# esp-boardlet.net
KiCad netlist of a schematic drawn in EAGLE
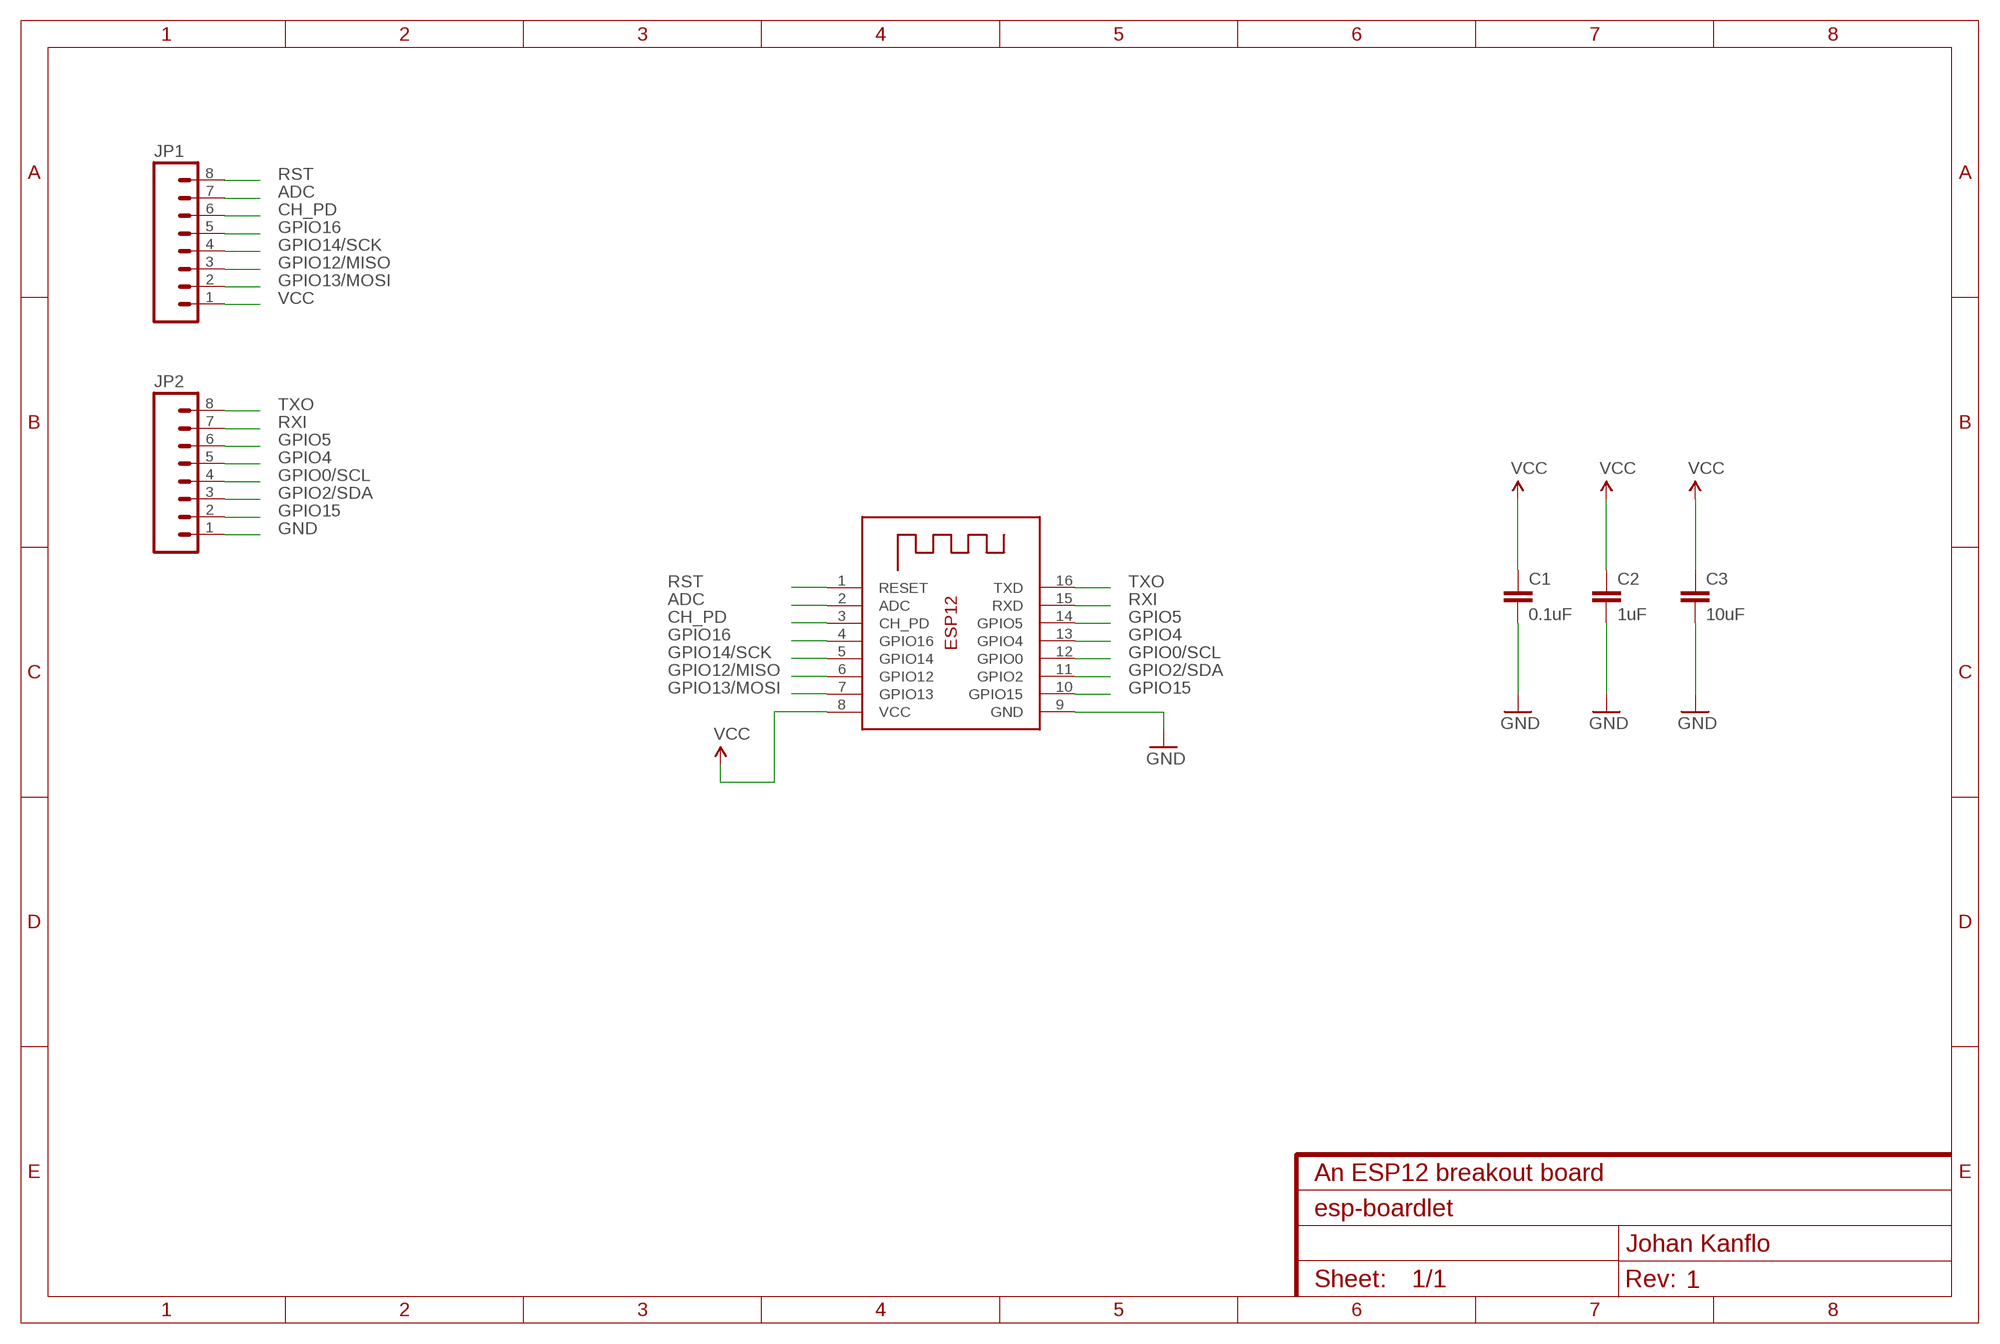
[diagram p0: schematic, sheet 1]

(export (version "E")
  (design (tool "Eeschema 10.0.6"))
  (components
    (comp (ref "C1")
      (value "0.1uF")
      (footprint "eagle-import:0603-CAP")
      (libsource (lib "eagle-import") (part "CAP0603-CAP"))
    )
    (comp (ref "C2")
      (value "1uF")
      (footprint "eagle-import:0603-CAP")
      (libsource (lib "eagle-import") (part "CAP0603-CAP"))
    )
    (comp (ref "C3")
      (value "10uF")
      (footprint "eagle-import:0603-CAP")
      (libsource (lib "eagle-import") (part "CAP0603-CAP"))
    )
    (comp (ref "JP1")
      (value "M08")
      (footprint "eagle-import:1X08_ROUND")
      (libsource (lib "eagle-import") (part "M08"))
    )
    (comp (ref "JP2")
      (value "M08")
      (footprint "eagle-import:1X08_ROUND")
      (libsource (lib "eagle-import") (part "M08"))
    )
    (comp (ref "X1")
      (value "ESP-12")
      (footprint "eagle-import:ESP-12")
      (libsource (lib "eagle-import") (part "ESP-12"))
    )
  )
  (nets
    (net (code "1") (name "/ADC") (class "Default")
      (node (ref "JP1") (pin "7") (pinfunction "7_7") (pintype "passive"))
      (node (ref "X1") (pin "2") (pinfunction "ADC_2") (pintype "passive"))
    )
    (net (code "2") (name "/CH_PD") (class "Default")
      (node (ref "JP1") (pin "6") (pinfunction "6_6") (pintype "passive"))
      (node (ref "X1") (pin "3") (pinfunction "CH_PD_3") (pintype "input"))
    )
    (net (code "3") (name "/GPIO0{slash}SCL") (class "Default")
      (node (ref "JP2") (pin "4") (pinfunction "4_4") (pintype "passive"))
      (node (ref "X1") (pin "12") (pinfunction "GPIO0_12") (pintype "bidirectional"))
    )
    (net (code "4") (name "/GPIO2{slash}SDA") (class "Default")
      (node (ref "JP2") (pin "3") (pinfunction "3_3") (pintype "passive"))
      (node (ref "X1") (pin "11") (pinfunction "GPIO2_11") (pintype "bidirectional"))
    )
    (net (code "5") (name "/GPIO4") (class "Default")
      (node (ref "JP2") (pin "5") (pinfunction "5_5") (pintype "passive"))
      (node (ref "X1") (pin "13") (pinfunction "GPIO4_13") (pintype "bidirectional"))
    )
    (net (code "6") (name "/GPIO5") (class "Default")
      (node (ref "JP2") (pin "6") (pinfunction "6_6") (pintype "passive"))
      (node (ref "X1") (pin "14") (pinfunction "GPIO5_14") (pintype "bidirectional"))
    )
    (net (code "7") (name "/GPIO12{slash}MISO") (class "Default")
      (node (ref "JP1") (pin "3") (pinfunction "3_3") (pintype "passive"))
      (node (ref "X1") (pin "6") (pinfunction "GPIO12_6") (pintype "bidirectional"))
    )
    (net (code "8") (name "/GPIO13{slash}MOSI") (class "Default")
      (node (ref "JP1") (pin "2") (pinfunction "2_2") (pintype "passive"))
      (node (ref "X1") (pin "7") (pinfunction "GPIO13_7") (pintype "bidirectional"))
    )
    (net (code "9") (name "/GPIO14{slash}SCK") (class "Default")
      (node (ref "JP1") (pin "4") (pinfunction "4_4") (pintype "passive"))
      (node (ref "X1") (pin "5") (pinfunction "GPIO14_5") (pintype "bidirectional"))
    )
    (net (code "10") (name "/GPIO15") (class "Default")
      (node (ref "JP2") (pin "2") (pinfunction "2_2") (pintype "passive"))
      (node (ref "X1") (pin "10") (pinfunction "GPIO15_10") (pintype "bidirectional"))
    )
    (net (code "11") (name "/GPIO16") (class "Default")
      (node (ref "JP1") (pin "5") (pinfunction "5_5") (pintype "passive"))
      (node (ref "X1") (pin "4") (pinfunction "GPIO16_4") (pintype "bidirectional"))
    )
    (net (code "12") (name "/RST") (class "Default")
      (node (ref "JP1") (pin "8") (pinfunction "8_8") (pintype "passive"))
      (node (ref "X1") (pin "1") (pinfunction "RESET_1") (pintype "input"))
    )
    (net (code "13") (name "/RXI") (class "Default")
      (node (ref "JP2") (pin "7") (pinfunction "7_7") (pintype "passive"))
      (node (ref "X1") (pin "15") (pinfunction "RXD_15") (pintype "input"))
    )
    (net (code "14") (name "/TXO") (class "Default")
      (node (ref "JP2") (pin "8") (pinfunction "8_8") (pintype "passive"))
      (node (ref "X1") (pin "16") (pinfunction "TXD_16") (pintype "output"))
    )
    (net (code "15") (name "GND") (class "Default")
      (node (ref "C1") (pin "2") (pinfunction "2_2") (pintype "passive"))
      (node (ref "C2") (pin "2") (pinfunction "2_2") (pintype "passive"))
      (node (ref "C3") (pin "2") (pinfunction "2_2") (pintype "passive"))
      (node (ref "JP2") (pin "1") (pinfunction "1_1") (pintype "passive"))
      (node (ref "X1") (pin "9") (pinfunction "GND_9") (pintype "power_in"))
    )
    (net (code "16") (name "VCC") (class "Default")
      (node (ref "C1") (pin "1") (pinfunction "1_1") (pintype "passive"))
      (node (ref "C2") (pin "1") (pinfunction "1_1") (pintype "passive"))
      (node (ref "C3") (pin "1") (pinfunction "1_1") (pintype "passive"))
      (node (ref "JP1") (pin "1") (pinfunction "1_1") (pintype "passive"))
      (node (ref "X1") (pin "8") (pinfunction "VCC_8") (pintype "power_in"))
    )
  )
)
